# sample-holder-pcb.net
KiCad netlist of a schematic drawn in EAGLE
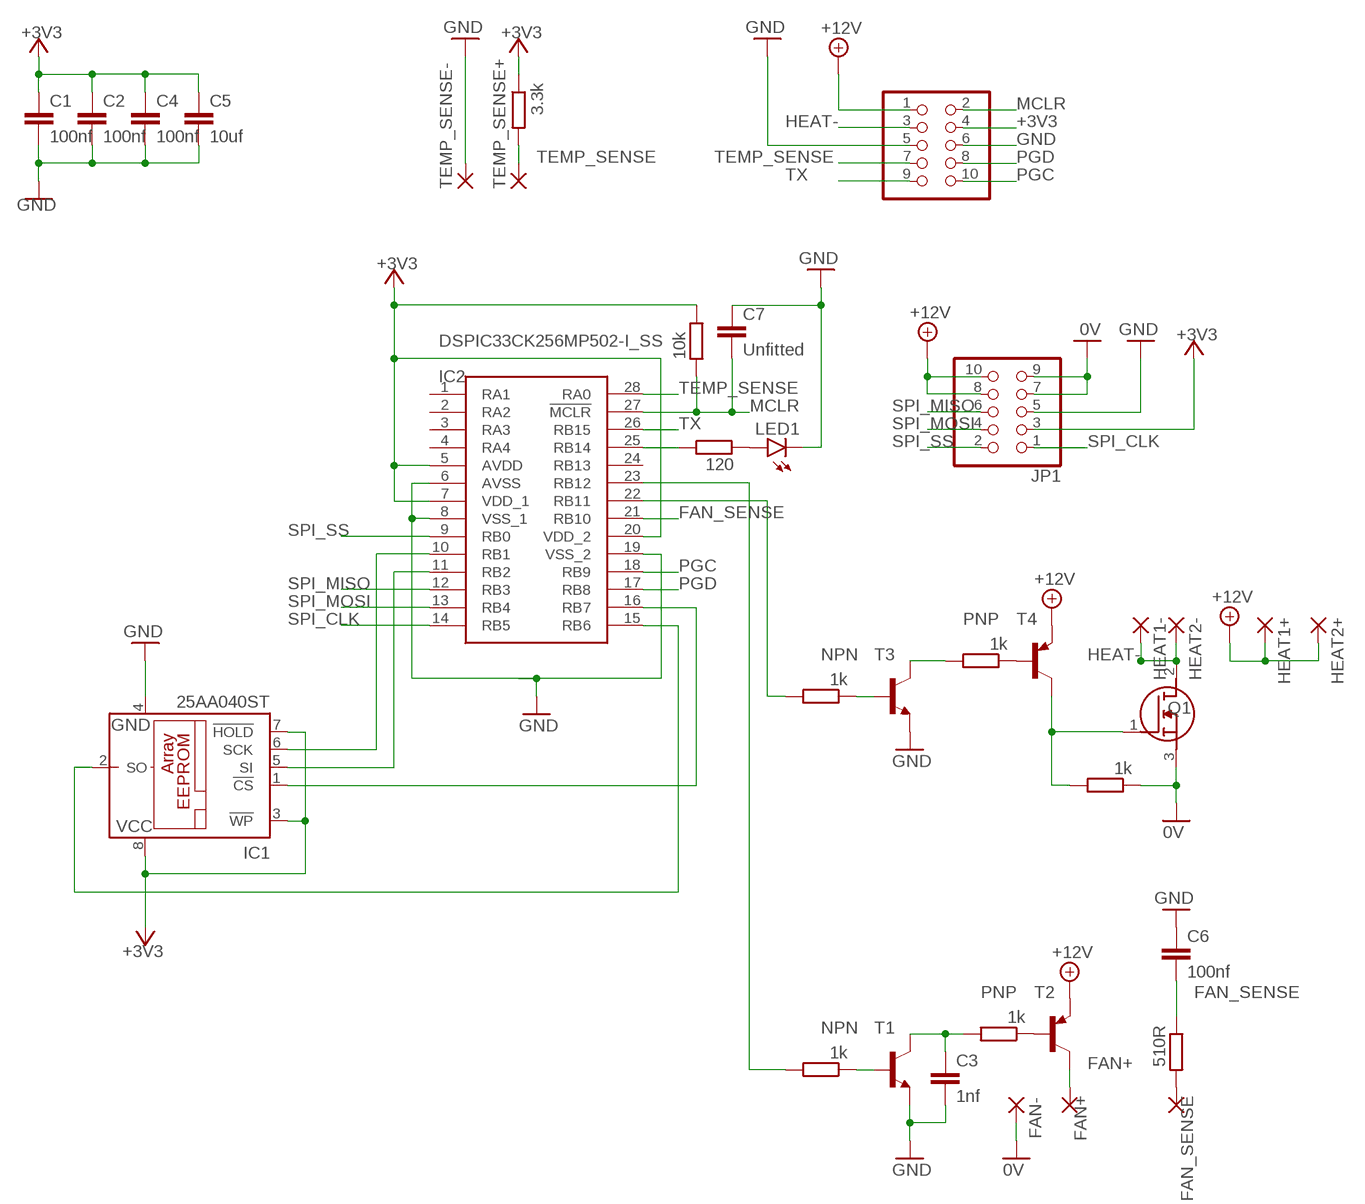
[diagram p0: schematic, sheet 1]

(export (version "E")
  (design (tool "Eeschema 10.0.6"))
  (components
    (comp (ref "C1")
      (value "100nf")
      (footprint "eagle-import:C0603")
      (libsource (lib "eagle-import") (part "C-EUC0603"))
    )
    (comp (ref "C2")
      (value "100nf")
      (footprint "eagle-import:C0603")
      (libsource (lib "eagle-import") (part "C-EUC0603"))
    )
    (comp (ref "C3")
      (value "1nf")
      (footprint "eagle-import:C0603")
      (libsource (lib "eagle-import") (part "C-EUC0603"))
    )
    (comp (ref "C4")
      (value "100nf")
      (footprint "eagle-import:C0603")
      (libsource (lib "eagle-import") (part "C-EUC0603"))
    )
    (comp (ref "C5")
      (value "10uf")
      (footprint "eagle-import:C1206")
      (libsource (lib "eagle-import") (part "C-EUC1206"))
    )
    (comp (ref "C6")
      (value "100nf")
      (footprint "eagle-import:C0603")
      (libsource (lib "eagle-import") (part "C-EUC0603"))
    )
    (comp (ref "C7")
      (value "Unfitted")
      (footprint "eagle-import:C0603")
      (libsource (lib "eagle-import") (part "C-EUC0603"))
    )
    (comp (ref "FAN+")
      (value "1,6/0,8")
      (footprint "eagle-import:1,6_0,8")
      (libsource (lib "eagle-import") (part "1,6/0,8"))
    )
    (comp (ref "FAN-")
      (value "1,6/0,8")
      (footprint "eagle-import:1,6_0,8")
      (libsource (lib "eagle-import") (part "1,6/0,8"))
    )
    (comp (ref "FAN_SENSE")
      (value "1,6/0,8")
      (footprint "eagle-import:1,6_0,8")
      (libsource (lib "eagle-import") (part "1,6/0,8"))
    )
    (comp (ref "HEAT1+")
      (value "2,54/1,0")
      (footprint "eagle-import:2,54_1,0")
      (libsource (lib "eagle-import") (part "2,54/1,0"))
    )
    (comp (ref "HEAT1-")
      (value "2,54/1,0")
      (footprint "eagle-import:2,54_1,0")
      (libsource (lib "eagle-import") (part "2,54/1,0"))
    )
    (comp (ref "HEAT2+")
      (value "2,54/1,0")
      (footprint "eagle-import:2,54_1,0")
      (libsource (lib "eagle-import") (part "2,54/1,0"))
    )
    (comp (ref "HEAT2-")
      (value "2,54/1,0")
      (footprint "eagle-import:2,54_1,0")
      (libsource (lib "eagle-import") (part "2,54/1,0"))
    )
    (comp (ref "IC1")
      (value "25AA040ST")
      (footprint "eagle-import:TSSOP8")
      (fields (field (name "MPN") "25AA040A-I/MS"))
      (libsource (lib "eagle-import") (part "25STAA040"))
    )
    (comp (ref "IC2")
      (value "DSPIC33CK256MP502-I_SS")
      (footprint "eagle-import:SOP65P780X200-28N")
      (fields
        (field (name "MANUFACTURER_PART_NUMBER") "dsPIC33CK256MP502-I/SS")
        (field (name "RS_PART_NUMBER") "1793987P")
      )
      (libsource (lib "eagle-import") (part "DSPIC33CK256MP502-I_SS"))
    )
    (comp (ref "JP1")
      (value "PINHD-2X5/90")
      (footprint "eagle-import:2X05_90")
      (libsource (lib "eagle-import") (part "PINHD-2X5/90"))
    )
    (comp (ref "JP2")
      (value "PINHD-2X5/90")
      (footprint "eagle-import:2X05_90")
      (libsource (lib "eagle-import") (part "PINHD-2X5/90"))
    )
    (comp (ref "LED1")
      (value "LEDSML0603")
      (footprint "eagle-import:SML0603")
      (libsource (lib "eagle-import") (part "LEDSML0603"))
    )
    (comp (ref "Q1")
      (value "AUIRFU8403")
      (footprint "eagle-import:TO229P239X654X978-3P")
      (libsource (lib "eagle-import") (part "AUIRFU8403"))
    )
    (comp (ref "R1")
      (value "1k")
      (footprint "eagle-import:R0603")
      (libsource (lib "eagle-import") (part "R-EU_R0603"))
    )
    (comp (ref "R2")
      (value "1k")
      (footprint "eagle-import:R0603")
      (libsource (lib "eagle-import") (part "R-EU_R0603"))
    )
    (comp (ref "R3")
      (value "1k")
      (footprint "eagle-import:R0603")
      (libsource (lib "eagle-import") (part "R-EU_R0603"))
    )
    (comp (ref "R4")
      (value "1k")
      (footprint "eagle-import:R0603")
      (libsource (lib "eagle-import") (part "R-EU_R0603"))
    )
    (comp (ref "R5")
      (value "1k")
      (footprint "eagle-import:R0603")
      (libsource (lib "eagle-import") (part "R-EU_R0603"))
    )
    (comp (ref "R6")
      (value "510R")
      (footprint "eagle-import:R0603")
      (libsource (lib "eagle-import") (part "R-EU_R0603"))
    )
    (comp (ref "R7")
      (value "3.3k")
      (footprint "eagle-import:R0603")
      (libsource (lib "eagle-import") (part "R-EU_R0603"))
    )
    (comp (ref "R8")
      (value "120")
      (footprint "eagle-import:R0603")
      (libsource (lib "eagle-import") (part "R-EU_R0603"))
    )
    (comp (ref "R9")
      (value "10k")
      (footprint "eagle-import:R0603")
      (libsource (lib "eagle-import") (part "R-EU_R0603"))
    )
    (comp (ref "T1")
      (value "NPN")
      (footprint "eagle-import:SOT23-BEC")
      (libsource (lib "eagle-import") (part "-NPN-SOT23-BECMMBT3904LT1"))
    )
    (comp (ref "T2")
      (value "PNP")
      (footprint "eagle-import:SOT23-BEC")
      (libsource (lib "eagle-import") (part "-PNP-SOT23-BECMMBT3906LT1"))
    )
    (comp (ref "T3")
      (value "NPN")
      (footprint "eagle-import:SOT23-BEC")
      (libsource (lib "eagle-import") (part "-NPN-SOT23-BECMMBT3904LT1"))
    )
    (comp (ref "T4")
      (value "PNP")
      (footprint "eagle-import:SOT23-BEC")
      (libsource (lib "eagle-import") (part "-PNP-SOT23-BECMMBT3906LT1"))
    )
    (comp (ref "TEMP_SENSE+")
      (value "1,6/0,8")
      (footprint "eagle-import:1,6_0,8")
      (libsource (lib "eagle-import") (part "1,6/0,8"))
    )
    (comp (ref "TEMP_SENSE-")
      (value "1,6/0,8")
      (footprint "eagle-import:1,6_0,8")
      (libsource (lib "eagle-import") (part "1,6/0,8"))
    )
  )
  (nets
    (net (code "1") (name "+3V3") (class "Default")
      (node (ref "C1") (pin "1") (pinfunction "1_1") (pintype "passive"))
      (node (ref "C2") (pin "1") (pinfunction "1_1") (pintype "passive"))
      (node (ref "C4") (pin "1") (pinfunction "1_1") (pintype "passive"))
      (node (ref "C5") (pin "1") (pinfunction "1_1") (pintype "passive"))
      (node (ref "IC1") (pin "3") (pinfunction "~{WP}_3") (pintype "input"))
      (node (ref "IC1") (pin "7") (pinfunction "~{HOLD}_7") (pintype "input"))
      (node (ref "IC1") (pin "8") (pinfunction "VCC_8") (pintype "power_in"))
      (node (ref "IC2") (pin "20") (pinfunction "VDD_2_20") (pintype "bidirectional"))
      (node (ref "IC2") (pin "5") (pinfunction "AVDD_5") (pintype "bidirectional"))
      (node (ref "IC2") (pin "7") (pinfunction "VDD_1_7") (pintype "bidirectional"))
      (node (ref "JP1") (pin "3") (pinfunction "3_3") (pintype "passive"))
      (node (ref "JP2") (pin "4") (pinfunction "4_4") (pintype "passive"))
      (node (ref "R7") (pin "1") (pinfunction "1_1") (pintype "passive"))
      (node (ref "R9") (pin "1") (pinfunction "1_1") (pintype "passive"))
    )
    (net (code "2") (name "+12V") (class "Default")
      (node (ref "HEAT1+") (pin "1") (pinfunction "P_1") (pintype "passive"))
      (node (ref "HEAT2+") (pin "1") (pinfunction "P_1") (pintype "passive"))
      (node (ref "JP1") (pin "10") (pinfunction "10_10") (pintype "passive"))
      (node (ref "JP1") (pin "8") (pinfunction "8_8") (pintype "passive"))
      (node (ref "JP2") (pin "1") (pinfunction "1_1") (pintype "passive"))
      (node (ref "T2") (pin "E") (pinfunction "E_E") (pintype "passive"))
      (node (ref "T4") (pin "E") (pinfunction "E_E") (pintype "passive"))
    )
    (net (code "3") (name "/FAN+") (class "Default")
      (node (ref "FAN+") (pin "1") (pinfunction "P_1") (pintype "passive"))
      (node (ref "T2") (pin "C") (pinfunction "C_C") (pintype "passive"))
    )
    (net (code "4") (name "/FAN_SENSE") (class "Default")
      (node (ref "C6") (pin "2") (pinfunction "2_2") (pintype "passive"))
      (node (ref "IC2") (pin "21") (pinfunction "RB10_21") (pintype "bidirectional"))
      (node (ref "R6") (pin "1") (pinfunction "1_1") (pintype "passive"))
    )
    (net (code "5") (name "/HEAT-") (class "Default")
      (node (ref "HEAT1-") (pin "1") (pinfunction "P_1") (pintype "passive"))
      (node (ref "HEAT2-") (pin "1") (pinfunction "P_1") (pintype "passive"))
      (node (ref "JP2") (pin "3") (pinfunction "3_3") (pintype "passive"))
      (node (ref "Q1") (pin "2") (pinfunction "D_2") (pintype "bidirectional"))
    )
    (net (code "6") (name "/MCLR") (class "Default")
      (node (ref "C7") (pin "2") (pinfunction "2_2") (pintype "passive"))
      (node (ref "IC2") (pin "27") (pinfunction "~{MCLR}_27") (pintype "bidirectional"))
      (node (ref "JP2") (pin "2") (pinfunction "2_2") (pintype "passive"))
      (node (ref "R9") (pin "2") (pinfunction "2_2") (pintype "passive"))
    )
    (net (code "7") (name "/PGC") (class "Default")
      (node (ref "IC2") (pin "18") (pinfunction "RB9_18") (pintype "bidirectional"))
      (node (ref "JP2") (pin "10") (pinfunction "10_10") (pintype "passive"))
    )
    (net (code "8") (name "/PGD") (class "Default")
      (node (ref "IC2") (pin "17") (pinfunction "RB8_17") (pintype "bidirectional"))
      (node (ref "JP2") (pin "8") (pinfunction "8_8") (pintype "passive"))
    )
    (net (code "9") (name "/SPI_CLK") (class "Default")
      (node (ref "IC2") (pin "14") (pinfunction "RB5_14") (pintype "bidirectional"))
      (node (ref "JP1") (pin "1") (pinfunction "1_1") (pintype "passive"))
    )
    (net (code "10") (name "/SPI_MISO") (class "Default")
      (node (ref "IC2") (pin "12") (pinfunction "RB3_12") (pintype "bidirectional"))
      (node (ref "JP1") (pin "6") (pinfunction "6_6") (pintype "passive"))
    )
    (net (code "11") (name "/SPI_MOSI") (class "Default")
      (node (ref "IC2") (pin "13") (pinfunction "RB4_13") (pintype "bidirectional"))
      (node (ref "JP1") (pin "4") (pinfunction "4_4") (pintype "passive"))
    )
    (net (code "12") (name "/SPI_SS") (class "Default")
      (node (ref "IC2") (pin "9") (pinfunction "RB0_9") (pintype "bidirectional"))
      (node (ref "JP1") (pin "2") (pinfunction "2_2") (pintype "passive"))
    )
    (net (code "13") (name "/TEMP_SENSE") (class "Default")
      (node (ref "IC2") (pin "28") (pinfunction "RA0_28") (pintype "bidirectional"))
      (node (ref "JP2") (pin "7") (pinfunction "7_7") (pintype "passive"))
      (node (ref "R7") (pin "2") (pinfunction "2_2") (pintype "passive"))
      (node (ref "TEMP_SENSE+") (pin "1") (pinfunction "P_1") (pintype "passive"))
    )
    (net (code "14") (name "/TX") (class "Default")
      (node (ref "IC2") (pin "26") (pinfunction "RB15_26") (pintype "bidirectional"))
      (node (ref "JP2") (pin "9") (pinfunction "9_9") (pintype "passive"))
    )
    (net (code "15") (name "0V") (class "Default")
      (node (ref "FAN-") (pin "1") (pinfunction "P_1") (pintype "passive"))
      (node (ref "JP1") (pin "7") (pinfunction "7_7") (pintype "passive"))
      (node (ref "JP1") (pin "9") (pinfunction "9_9") (pintype "passive"))
      (node (ref "Q1") (pin "3") (pinfunction "S_3") (pintype "bidirectional"))
      (node (ref "R5") (pin "1") (pinfunction "1_1") (pintype "passive"))
    )
    (net (code "16") (name "GND") (class "Default")
      (node (ref "C1") (pin "2") (pinfunction "2_2") (pintype "passive"))
      (node (ref "C2") (pin "2") (pinfunction "2_2") (pintype "passive"))
      (node (ref "C3") (pin "2") (pinfunction "2_2") (pintype "passive"))
      (node (ref "C4") (pin "2") (pinfunction "2_2") (pintype "passive"))
      (node (ref "C5") (pin "2") (pinfunction "2_2") (pintype "passive"))
      (node (ref "C6") (pin "1") (pinfunction "1_1") (pintype "passive"))
      (node (ref "C7") (pin "1") (pinfunction "1_1") (pintype "passive"))
      (node (ref "IC1") (pin "4") (pinfunction "GND_4") (pintype "power_in"))
      (node (ref "IC2") (pin "19") (pinfunction "VSS_2_19") (pintype "bidirectional"))
      (node (ref "IC2") (pin "6") (pinfunction "AVSS_6") (pintype "bidirectional"))
      (node (ref "IC2") (pin "8") (pinfunction "VSS_1_8") (pintype "bidirectional"))
      (node (ref "JP1") (pin "5") (pinfunction "5_5") (pintype "passive"))
      (node (ref "JP2") (pin "5") (pinfunction "5_5") (pintype "passive"))
      (node (ref "JP2") (pin "6") (pinfunction "6_6") (pintype "passive"))
      (node (ref "LED1") (pin "C") (pinfunction "C_C") (pintype "passive"))
      (node (ref "T1") (pin "E") (pinfunction "E_E") (pintype "passive"))
      (node (ref "T3") (pin "E") (pinfunction "E_E") (pintype "passive"))
      (node (ref "TEMP_SENSE-") (pin "1") (pinfunction "P_1") (pintype "passive"))
    )
    (net (code "17") (name "Net-(C3-Pad1)") (class "Default")
      (node (ref "C3") (pin "1") (pinfunction "1_1") (pintype "passive"))
      (node (ref "R3") (pin "2") (pinfunction "2_2") (pintype "passive"))
      (node (ref "T1") (pin "C") (pinfunction "C_C") (pintype "passive"))
    )
    (net (code "18") (name "Net-(FAN_SENSE-P)") (class "Default")
      (node (ref "FAN_SENSE") (pin "1") (pinfunction "P_1") (pintype "passive"))
      (node (ref "R6") (pin "2") (pinfunction "2_2") (pintype "passive"))
    )
    (net (code "19") (name "Net-(IC1-SCK)") (class "Default")
      (node (ref "IC1") (pin "6") (pinfunction "SCK_6") (pintype "input"))
      (node (ref "IC2") (pin "10") (pinfunction "RB1_10") (pintype "bidirectional"))
    )
    (net (code "20") (name "Net-(IC1-SI)") (class "Default")
      (node (ref "IC1") (pin "5") (pinfunction "SI_5") (pintype "input"))
      (node (ref "IC2") (pin "11") (pinfunction "RB2_11") (pintype "bidirectional"))
    )
    (net (code "21") (name "Net-(IC1-SO)") (class "Default")
      (node (ref "IC1") (pin "2") (pinfunction "SO_2") (pintype "bidirectional"))
      (node (ref "IC2") (pin "15") (pinfunction "RB6_15") (pintype "bidirectional"))
    )
    (net (code "22") (name "Net-(IC1-~{CS})") (class "Default")
      (node (ref "IC1") (pin "1") (pinfunction "~{CS}_1") (pintype "input"))
      (node (ref "IC2") (pin "16") (pinfunction "RB7_16") (pintype "bidirectional"))
    )
    (net (code "23") (name "Net-(IC2-RB11)") (class "Default")
      (node (ref "IC2") (pin "22") (pinfunction "RB11_22") (pintype "bidirectional"))
      (node (ref "R2") (pin "2") (pinfunction "2_2") (pintype "passive"))
    )
    (net (code "24") (name "Net-(IC2-RB12)") (class "Default")
      (node (ref "IC2") (pin "23") (pinfunction "RB12_23") (pintype "bidirectional"))
      (node (ref "R1") (pin "2") (pinfunction "2_2") (pintype "passive"))
    )
    (net (code "25") (name "Net-(IC2-RB14)") (class "Default")
      (node (ref "IC2") (pin "25") (pinfunction "RB14_25") (pintype "bidirectional"))
      (node (ref "R8") (pin "1") (pinfunction "1_1") (pintype "passive"))
    )
    (net (code "26") (name "Net-(LED1-PadA)") (class "Default")
      (node (ref "LED1") (pin "A") (pinfunction "A_A") (pintype "passive"))
      (node (ref "R8") (pin "2") (pinfunction "2_2") (pintype "passive"))
    )
    (net (code "27") (name "Net-(Q1-G)") (class "Default")
      (node (ref "Q1") (pin "1") (pinfunction "G_1") (pintype "bidirectional"))
      (node (ref "R5") (pin "2") (pinfunction "2_2") (pintype "passive"))
      (node (ref "T4") (pin "C") (pinfunction "C_C") (pintype "passive"))
    )
    (net (code "28") (name "Net-(R1-Pad1)") (class "Default")
      (node (ref "R1") (pin "1") (pinfunction "1_1") (pintype "passive"))
      (node (ref "T1") (pin "B") (pinfunction "B_B") (pintype "passive"))
    )
    (net (code "29") (name "Net-(R2-Pad1)") (class "Default")
      (node (ref "R2") (pin "1") (pinfunction "1_1") (pintype "passive"))
      (node (ref "T3") (pin "B") (pinfunction "B_B") (pintype "passive"))
    )
    (net (code "30") (name "Net-(R3-Pad1)") (class "Default")
      (node (ref "R3") (pin "1") (pinfunction "1_1") (pintype "passive"))
      (node (ref "T2") (pin "B") (pinfunction "B_B") (pintype "passive"))
    )
    (net (code "31") (name "Net-(R4-Pad1)") (class "Default")
      (node (ref "R4") (pin "1") (pinfunction "1_1") (pintype "passive"))
      (node (ref "T4") (pin "B") (pinfunction "B_B") (pintype "passive"))
    )
    (net (code "32") (name "Net-(R4-Pad2)") (class "Default")
      (node (ref "R4") (pin "2") (pinfunction "2_2") (pintype "passive"))
      (node (ref "T3") (pin "C") (pinfunction "C_C") (pintype "passive"))
    )
    (net (code "33") (name "unconnected-(IC2-RA1-Pad1)") (class "Default")
      (node (ref "IC2") (pin "1") (pinfunction "RA1_1") (pintype "bidirectional"))
    )
    (net (code "34") (name "unconnected-(IC2-RA2-Pad2)") (class "Default")
      (node (ref "IC2") (pin "2") (pinfunction "RA2_2") (pintype "bidirectional"))
    )
    (net (code "35") (name "unconnected-(IC2-RA3-Pad3)") (class "Default")
      (node (ref "IC2") (pin "3") (pinfunction "RA3_3") (pintype "bidirectional"))
    )
    (net (code "36") (name "unconnected-(IC2-RA4-Pad4)") (class "Default")
      (node (ref "IC2") (pin "4") (pinfunction "RA4_4") (pintype "bidirectional"))
    )
    (net (code "37") (name "unconnected-(IC2-RB13-Pad24)") (class "Default")
      (node (ref "IC2") (pin "24") (pinfunction "RB13_24") (pintype "bidirectional"))
    )
  )
)
